# openmote32_2_0_1.net
KiCad netlist of a schematic drawn in EAGLE
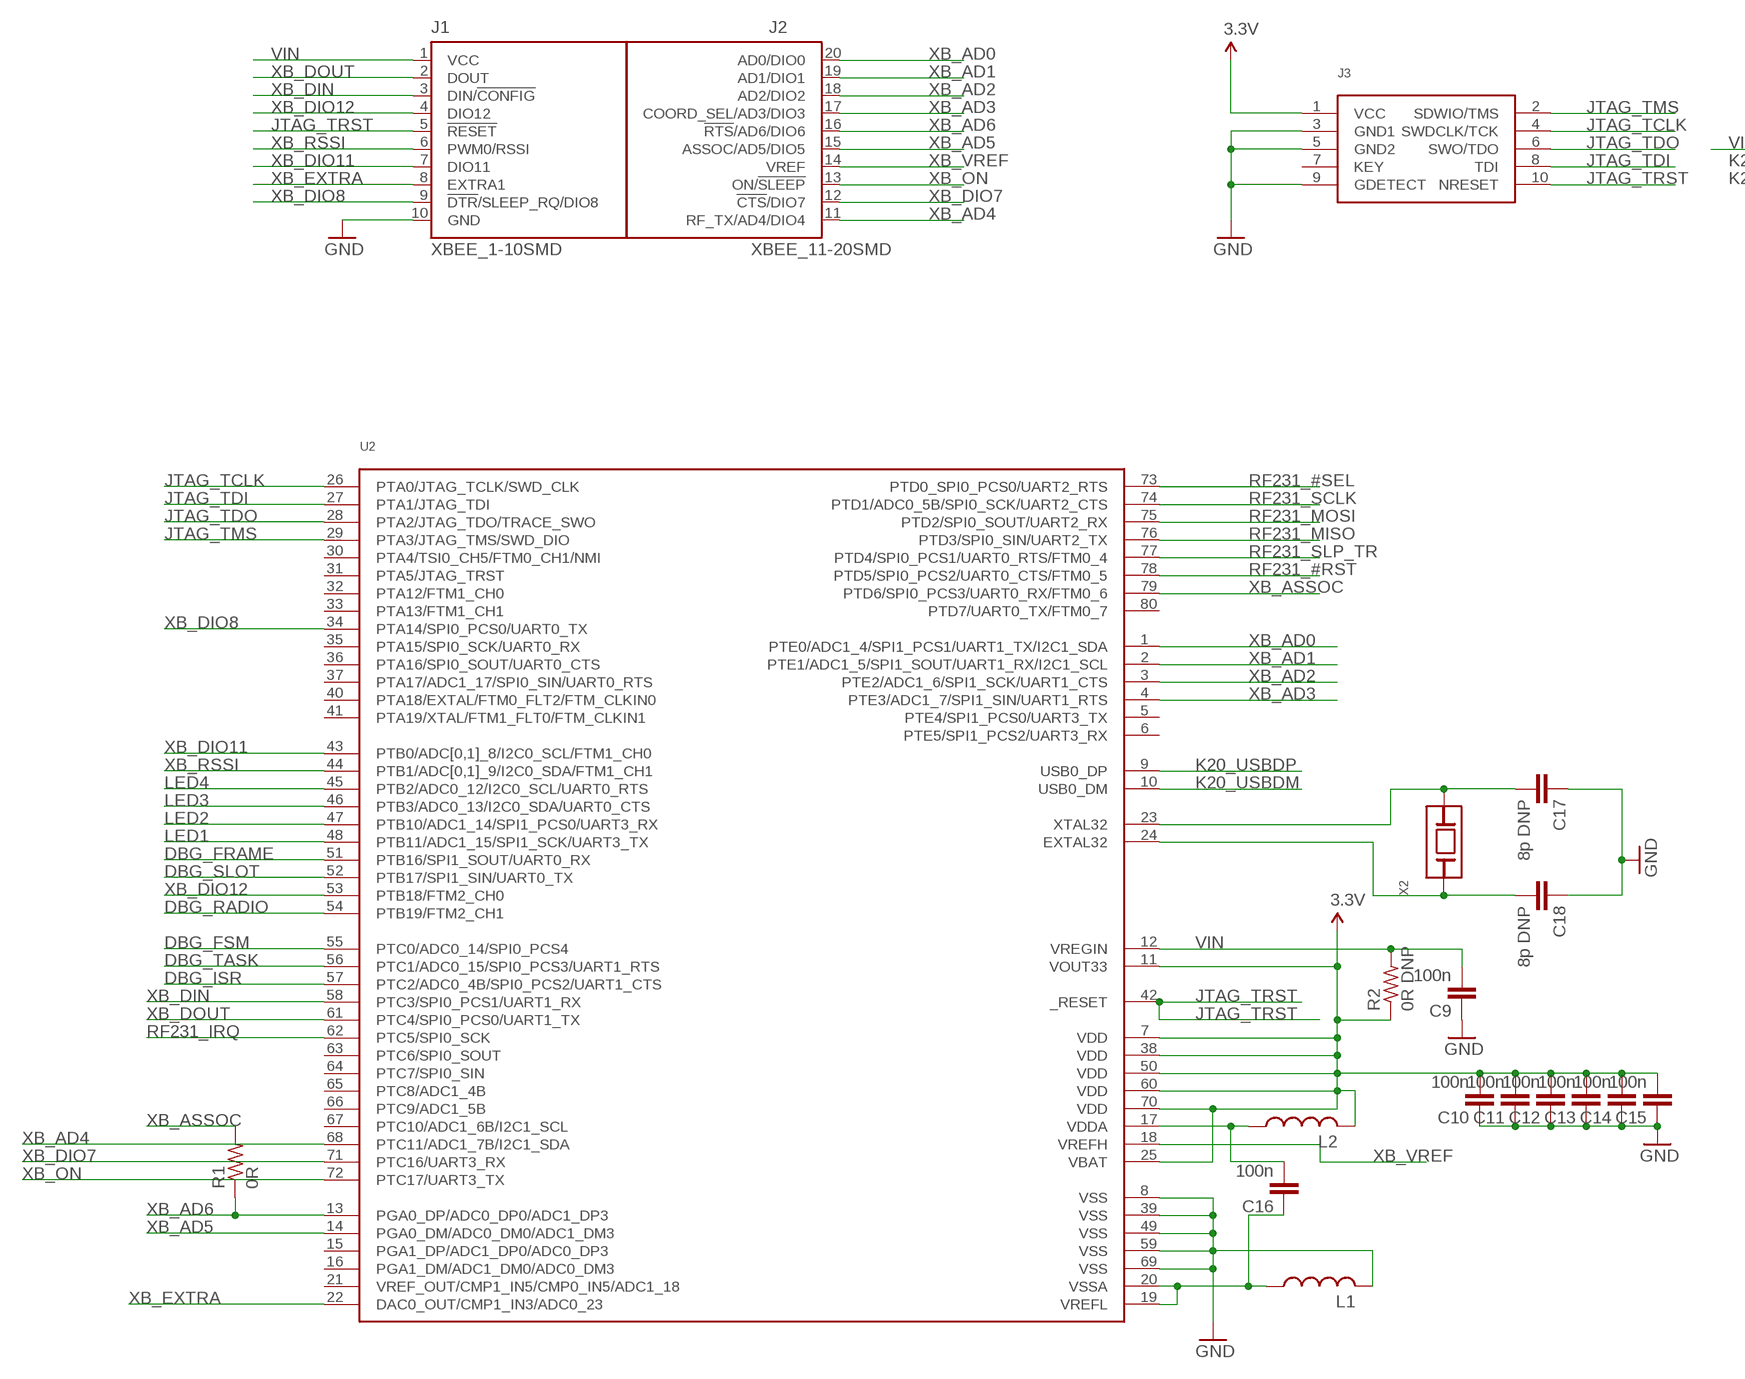
[diagram p0: schematic, sheet 1, part 1 of 2]
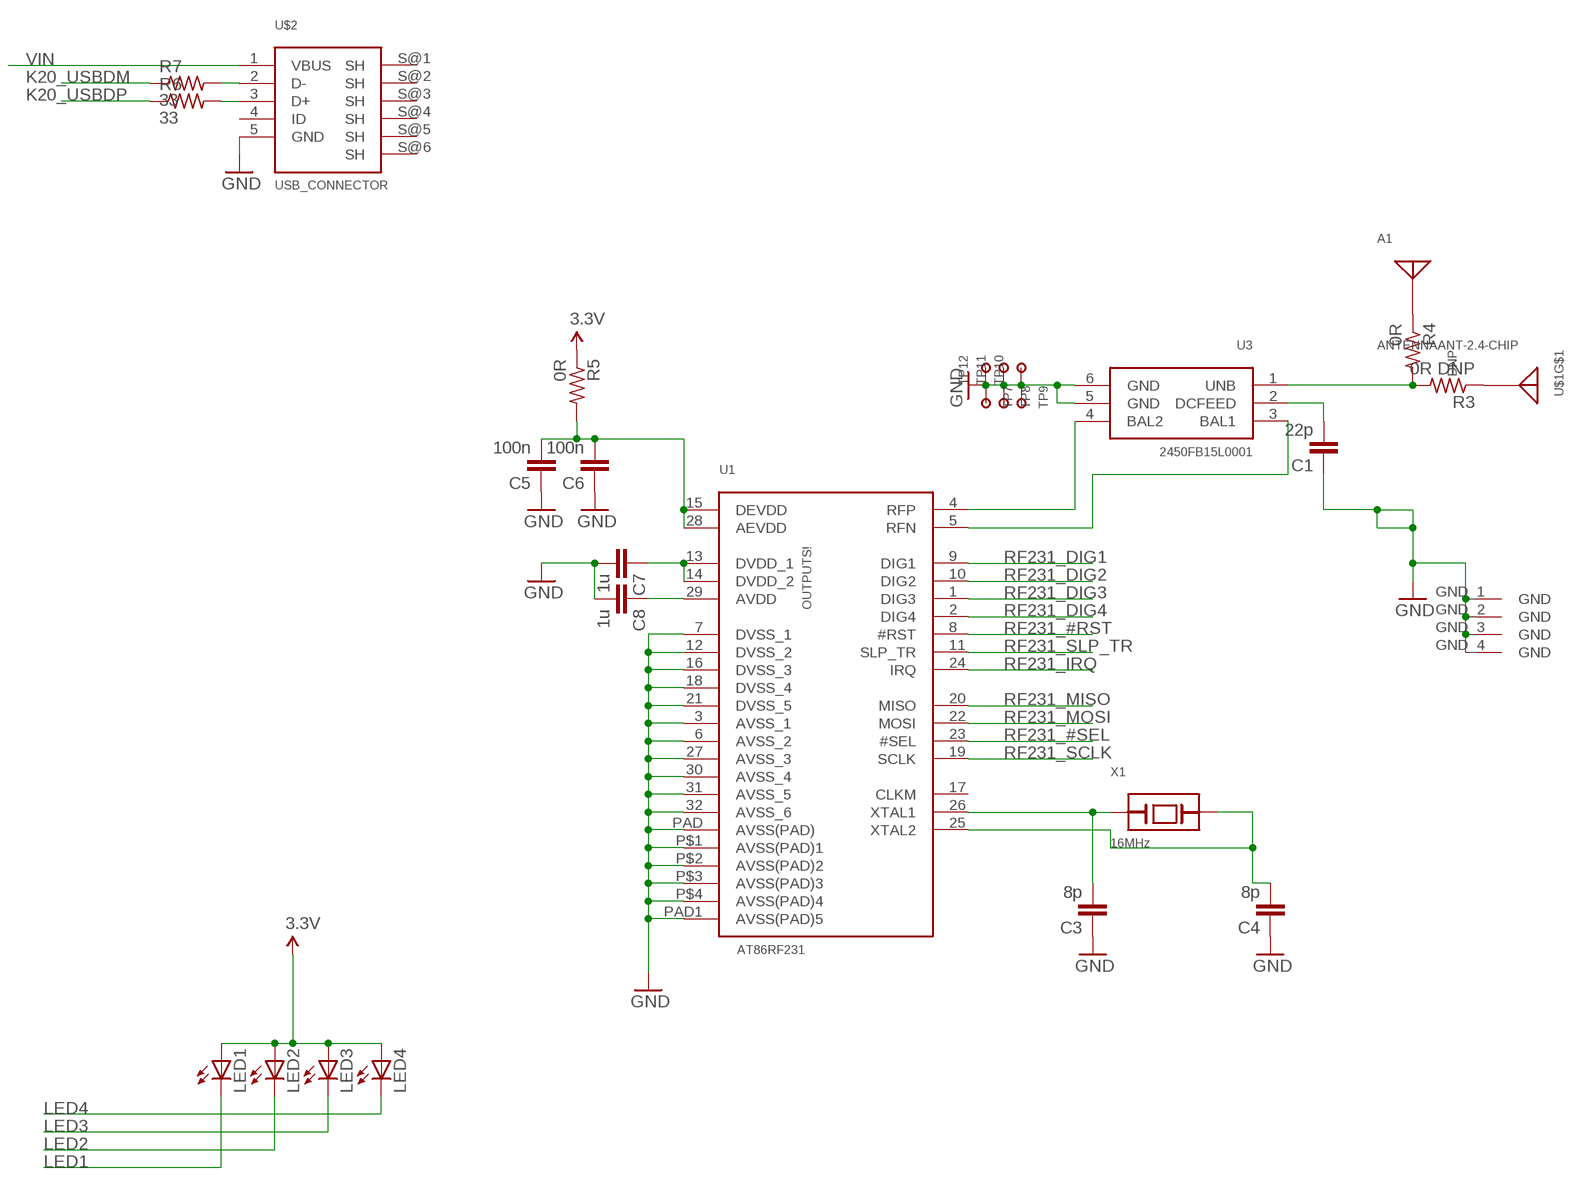
[diagram p1: schematic, sheet 1, part 2 of 2]

(export (version "E")
  (design (tool "Eeschema 10.0.6"))
  (components
    (comp (ref "A1")
      (value "ANTENNAANT-2.4-CHIP")
      (footprint "eagle-import:ANT-2.4-CHP")
      (libsource (lib "eagle-import") (part "ANTENNAANT-2.4-CHIP"))
    )
    (comp (ref "C1")
      (value "22p")
      (footprint "eagle-import:C0402")
      (libsource (lib "eagle-import") (part "CAP0402"))
    )
    (comp (ref "C3")
      (value "8p")
      (footprint "eagle-import:C0402")
      (libsource (lib "eagle-import") (part "CAP0402"))
    )
    (comp (ref "C4")
      (value "8p")
      (footprint "eagle-import:C0402")
      (libsource (lib "eagle-import") (part "CAP0402"))
    )
    (comp (ref "C5")
      (value "100n")
      (footprint "eagle-import:C0402")
      (libsource (lib "eagle-import") (part "CAP0402"))
    )
    (comp (ref "C6")
      (value "100n")
      (footprint "eagle-import:C0402")
      (libsource (lib "eagle-import") (part "CAP0402"))
    )
    (comp (ref "C7")
      (value "1u")
      (footprint "eagle-import:C0402")
      (libsource (lib "eagle-import") (part "CAP0402"))
    )
    (comp (ref "C8")
      (value "1u")
      (footprint "eagle-import:C0402")
      (libsource (lib "eagle-import") (part "CAP0402"))
    )
    (comp (ref "C9")
      (value "100n")
      (footprint "eagle-import:C0402")
      (libsource (lib "eagle-import") (part "CAP0402"))
    )
    (comp (ref "C10")
      (value "100n")
      (footprint "eagle-import:C0402")
      (libsource (lib "eagle-import") (part "CAP0402"))
    )
    (comp (ref "C11")
      (value "100n")
      (footprint "eagle-import:C0402")
      (libsource (lib "eagle-import") (part "CAP0402"))
    )
    (comp (ref "C12")
      (value "100n")
      (footprint "eagle-import:C0402")
      (libsource (lib "eagle-import") (part "CAP0402"))
    )
    (comp (ref "C13")
      (value "100n")
      (footprint "eagle-import:C0402")
      (libsource (lib "eagle-import") (part "CAP0402"))
    )
    (comp (ref "C14")
      (value "100n")
      (footprint "eagle-import:C0402")
      (libsource (lib "eagle-import") (part "CAP0402"))
    )
    (comp (ref "C15")
      (value "100n")
      (footprint "eagle-import:C0402")
      (libsource (lib "eagle-import") (part "CAP0402"))
    )
    (comp (ref "C16")
      (value "100n")
      (footprint "eagle-import:C0402")
      (libsource (lib "eagle-import") (part "CAP0402"))
    )
    (comp (ref "C17")
      (value "8p DNP")
      (footprint "eagle-import:C0402")
      (libsource (lib "eagle-import") (part "CAP0402"))
    )
    (comp (ref "C18")
      (value "8p DNP")
      (footprint "eagle-import:C0402")
      (libsource (lib "eagle-import") (part "CAP0402"))
    )
    (comp (ref "J1")
      (value "XBEE_1-10SMD")
      (footprint "eagle-import:XBEE_1-10+SMD")
      (libsource (lib "eagle-import") (part "XBEE_1-10SMD"))
    )
    (comp (ref "J2")
      (value "XBEE_11-20SMD")
      (footprint "eagle-import:XBEE_11-20+SMD")
      (libsource (lib "eagle-import") (part "XBEE_11-20SMD"))
    )
    (comp (ref "J3")
      (value "JTAG_CONNECTOR")
      (footprint "eagle-import:SMD-050-HEADER-2X5")
      (libsource (lib "eagle-import") (part "JTAG_CONNECTOR"))
    )
    (comp (ref "L1")
      (value "L-USL0402")
      (footprint "eagle-import:L0402")
      (libsource (lib "eagle-import") (part "L-USL0402"))
    )
    (comp (ref "L2")
      (value "L-USL0402")
      (footprint "eagle-import:L0402")
      (libsource (lib "eagle-import") (part "L-USL0402"))
    )
    (comp (ref "LED1")
      (value "LEDCHIPLED_0603")
      (footprint "eagle-import:CHIPLED_0603")
      (libsource (lib "eagle-import") (part "LEDCHIPLED_0603"))
    )
    (comp (ref "LED2")
      (value "LEDCHIPLED_0603")
      (footprint "eagle-import:CHIPLED_0603")
      (libsource (lib "eagle-import") (part "LEDCHIPLED_0603"))
    )
    (comp (ref "LED3")
      (value "LEDCHIPLED_0603")
      (footprint "eagle-import:CHIPLED_0603")
      (libsource (lib "eagle-import") (part "LEDCHIPLED_0603"))
    )
    (comp (ref "LED4")
      (value "LEDCHIPLED_0603")
      (footprint "eagle-import:CHIPLED_0603")
      (libsource (lib "eagle-import") (part "LEDCHIPLED_0603"))
    )
    (comp (ref "R1")
      (value "0R")
      (footprint "eagle-import:R0402")
      (libsource (lib "eagle-import") (part "R-US_R0402"))
    )
    (comp (ref "R2")
      (value "0R DNP")
      (footprint "eagle-import:R0402")
      (libsource (lib "eagle-import") (part "R-US_R0402"))
    )
    (comp (ref "R3")
      (value "0R DNP")
      (footprint "eagle-import:R0402")
      (libsource (lib "eagle-import") (part "R-US_R0402"))
    )
    (comp (ref "R4")
      (value "0R")
      (footprint "eagle-import:R0402")
      (libsource (lib "eagle-import") (part "R-US_R0402"))
    )
    (comp (ref "R5")
      (value "0R")
      (footprint "eagle-import:R0402")
      (libsource (lib "eagle-import") (part "R-US_R0402"))
    )
    (comp (ref "R6")
      (value "33")
      (footprint "eagle-import:R0402")
      (libsource (lib "eagle-import") (part "R-US_R0402"))
    )
    (comp (ref "R7")
      (value "33")
      (footprint "eagle-import:R0402")
      (libsource (lib "eagle-import") (part "R-US_R0402"))
    )
    (comp (ref "TP7")
      (value "TESTPOINTSMALLEST")
      (footprint "eagle-import:TESTPOINT")
      (libsource (lib "eagle-import") (part "TESTPOINTSMALLEST"))
    )
    (comp (ref "TP8")
      (value "TESTPOINTSMALLEST")
      (footprint "eagle-import:TESTPOINT")
      (libsource (lib "eagle-import") (part "TESTPOINTSMALLEST"))
    )
    (comp (ref "TP9")
      (value "TESTPOINTSMALLEST")
      (footprint "eagle-import:TESTPOINT")
      (libsource (lib "eagle-import") (part "TESTPOINTSMALLEST"))
    )
    (comp (ref "TP10")
      (value "TESTPOINTSMALLEST")
      (footprint "eagle-import:TESTPOINT")
      (libsource (lib "eagle-import") (part "TESTPOINTSMALLEST"))
    )
    (comp (ref "TP11")
      (value "TESTPOINTSMALLEST")
      (footprint "eagle-import:TESTPOINT")
      (libsource (lib "eagle-import") (part "TESTPOINTSMALLEST"))
    )
    (comp (ref "TP12")
      (value "TESTPOINTSMALLEST")
      (footprint "eagle-import:TESTPOINT")
      (libsource (lib "eagle-import") (part "TESTPOINTSMALLEST"))
    )
    (comp (ref "U$1")
      (value "DNP")
      (footprint "eagle-import:CONREVSMA003.031")
      (libsource (lib "eagle-import") (part "ANTENNA_W_GROUNDS"))
    )
    (comp (ref "U$2")
      (value "USB_CONNECTOR")
      (footprint "eagle-import:MICROUSB_10118192")
      (libsource (lib "eagle-import") (part "USB_CONNECTOR"))
    )
    (comp (ref "U1")
      (value "AT86RF231")
      (footprint "eagle-import:ATRF231_32QN2")
      (libsource (lib "eagle-import") (part "AT86RF231"))
    )
    (comp (ref "U2")
      (value "K20_80PIN")
      (footprint "eagle-import:K20_LQFP80")
      (libsource (lib "eagle-import") (part "K20_80PIN"))
    )
    (comp (ref "U3")
      (value "2450FB15L0001")
      (footprint "eagle-import:2450FB15L0001")
      (libsource (lib "eagle-import") (part "2450FB15L0001"))
    )
    (comp (ref "X1")
      (value "16MHz")
      (footprint "eagle-import:CX3225SA")
      (libsource (lib "eagle-import") (part "XTALCX3225SA"))
    )
    (comp (ref "X2")
      (value "XTALABS07")
      (footprint "eagle-import:ABS07")
      (libsource (lib "eagle-import") (part "XTALABS07"))
    )
  )
  (nets
    (net (code "1") (name "/DBG_FRAME") (class "Default")
      (node (ref "U2") (pin "51") (pinfunction "PTB16/SPI1_SOUT/UART0_RX_51") (pintype "bidirectional"))
    )
    (net (code "2") (name "/DBG_FSM") (class "Default")
      (node (ref "U2") (pin "55") (pinfunction "PTC0/ADC0_14/SPI0_PCS4_55") (pintype "bidirectional"))
    )
    (net (code "3") (name "/DBG_ISR") (class "Default")
      (node (ref "U2") (pin "57") (pinfunction "PTC2/ADC0_4B/SPI0_PCS2/UART1_CTS_57") (pintype "bidirectional"))
    )
    (net (code "4") (name "/DBG_RADIO") (class "Default")
      (node (ref "U2") (pin "54") (pinfunction "PTB19/FTM2_CH1_54") (pintype "bidirectional"))
    )
    (net (code "5") (name "/DBG_SLOT") (class "Default")
      (node (ref "U2") (pin "52") (pinfunction "PTB17/SPI1_SIN/UART0_TX_52") (pintype "bidirectional"))
    )
    (net (code "6") (name "/DBG_TASK") (class "Default")
      (node (ref "U2") (pin "56") (pinfunction "PTC1/ADC0_15/SPI0_PCS3/UART1_RTS_56") (pintype "bidirectional"))
    )
    (net (code "7") (name "/JTAG_TCLK") (class "Default")
      (node (ref "J3") (pin "4") (pinfunction "SWDCLK/TCK_4") (pintype "bidirectional"))
      (node (ref "U2") (pin "26") (pinfunction "PTA0/JTAG_TCLK/SWD_CLK_26") (pintype "bidirectional"))
    )
    (net (code "8") (name "/JTAG_TDI") (class "Default")
      (node (ref "J3") (pin "8") (pinfunction "TDI_8") (pintype "bidirectional"))
      (node (ref "U2") (pin "27") (pinfunction "PTA1/JTAG_TDI_27") (pintype "bidirectional"))
    )
    (net (code "9") (name "/JTAG_TDO") (class "Default")
      (node (ref "J3") (pin "6") (pinfunction "SWO/TDO_6") (pintype "bidirectional"))
      (node (ref "U2") (pin "28") (pinfunction "PTA2/JTAG_TDO/TRACE_SWO_28") (pintype "bidirectional"))
    )
    (net (code "10") (name "/JTAG_TMS") (class "Default")
      (node (ref "J3") (pin "2") (pinfunction "SDWIO/TMS_2") (pintype "bidirectional"))
      (node (ref "U2") (pin "29") (pinfunction "PTA3/JTAG_TMS/SWD_DIO_29") (pintype "bidirectional"))
    )
    (net (code "11") (name "/JTAG_TRST") (class "Default")
      (node (ref "J1") (pin "5") (pinfunction "~{RESET}_5") (pintype "input"))
      (node (ref "J3") (pin "10") (pinfunction "NRESET_10") (pintype "bidirectional"))
      (node (ref "U2") (pin "42") (pinfunction "_RESET_42") (pintype "bidirectional"))
    )
    (net (code "12") (name "/K20_USBDM") (class "Default")
      (node (ref "R7") (pin "1") (pinfunction "1_1") (pintype "passive"))
      (node (ref "U2") (pin "10") (pinfunction "USB0_DM_10") (pintype "bidirectional"))
    )
    (net (code "13") (name "/K20_USBDP") (class "Default")
      (node (ref "R6") (pin "1") (pinfunction "1_1") (pintype "passive"))
      (node (ref "U2") (pin "9") (pinfunction "USB0_DP_9") (pintype "bidirectional"))
    )
    (net (code "14") (name "/LED1") (class "Default")
      (node (ref "LED1") (pin "C") (pinfunction "C_C") (pintype "passive"))
      (node (ref "U2") (pin "48") (pinfunction "PTB11/ADC1_15/SPI1_SCK/UART3_TX_48") (pintype "bidirectional"))
    )
    (net (code "15") (name "/LED2") (class "Default")
      (node (ref "LED2") (pin "C") (pinfunction "C_C") (pintype "passive"))
      (node (ref "U2") (pin "47") (pinfunction "PTB10/ADC1_14/SPI1_PCS0/UART3_RX_47") (pintype "bidirectional"))
    )
    (net (code "16") (name "/LED3") (class "Default")
      (node (ref "LED3") (pin "C") (pinfunction "C_C") (pintype "passive"))
      (node (ref "U2") (pin "46") (pinfunction "PTB3/ADC0_13/I2C0_SDA/UART0_CTS_46") (pintype "bidirectional"))
    )
    (net (code "17") (name "/LED4") (class "Default")
      (node (ref "LED4") (pin "C") (pinfunction "C_C") (pintype "passive"))
      (node (ref "U2") (pin "45") (pinfunction "PTB2/ADC0_12/I2C0_SCL/UART0_RTS_45") (pintype "bidirectional"))
    )
    (net (code "18") (name "/RF231_#RST") (class "Default")
      (node (ref "U1") (pin "8") (pinfunction "#RST_8") (pintype "bidirectional"))
      (node (ref "U2") (pin "78") (pinfunction "PTD5/SPI0_PCS2/UART0_CTS/FTM0_5_78") (pintype "bidirectional"))
    )
    (net (code "19") (name "/RF231_#SEL") (class "Default")
      (node (ref "U1") (pin "23") (pinfunction "#SEL_23") (pintype "bidirectional"))
      (node (ref "U2") (pin "73") (pinfunction "PTD0_SPI0_PCS0/UART2_RTS_73") (pintype "bidirectional"))
    )
    (net (code "20") (name "/RF231_DIG1") (class "Default")
      (node (ref "U1") (pin "9") (pinfunction "DIG1_9") (pintype "bidirectional"))
    )
    (net (code "21") (name "/RF231_DIG2") (class "Default")
      (node (ref "U1") (pin "10") (pinfunction "DIG2_10") (pintype "bidirectional"))
    )
    (net (code "22") (name "/RF231_DIG3") (class "Default")
      (node (ref "U1") (pin "1") (pinfunction "DIG3_1") (pintype "bidirectional"))
    )
    (net (code "23") (name "/RF231_DIG4") (class "Default")
      (node (ref "U1") (pin "2") (pinfunction "DIG4_2") (pintype "bidirectional"))
    )
    (net (code "24") (name "/RF231_IRQ") (class "Default")
      (node (ref "U1") (pin "24") (pinfunction "IRQ_24") (pintype "bidirectional"))
      (node (ref "U2") (pin "62") (pinfunction "PTC5/SPI0_SCK_62") (pintype "bidirectional"))
    )
    (net (code "25") (name "/RF231_MISO") (class "Default")
      (node (ref "U1") (pin "20") (pinfunction "MISO_20") (pintype "bidirectional"))
      (node (ref "U2") (pin "76") (pinfunction "PTD3/SPI0_SIN/UART2_TX_76") (pintype "bidirectional"))
    )
    (net (code "26") (name "/RF231_MOSI") (class "Default")
      (node (ref "U1") (pin "22") (pinfunction "MOSI_22") (pintype "bidirectional"))
      (node (ref "U2") (pin "75") (pinfunction "PTD2/SPI0_SOUT/UART2_RX_75") (pintype "bidirectional"))
    )
    (net (code "27") (name "/RF231_SCLK") (class "Default")
      (node (ref "U1") (pin "19") (pinfunction "SCLK_19") (pintype "bidirectional"))
      (node (ref "U2") (pin "74") (pinfunction "PTD1/ADC0_5B/SPI0_SCK/UART2_CTS_74") (pintype "bidirectional"))
    )
    (net (code "28") (name "/RF231_SLP_TR") (class "Default")
      (node (ref "U1") (pin "11") (pinfunction "SLP_TR_11") (pintype "bidirectional"))
      (node (ref "U2") (pin "77") (pinfunction "PTD4/SPI0_PCS1/UART0_RTS/FTM0_4_77") (pintype "bidirectional"))
    )
    (net (code "29") (name "/VIN") (class "Default")
      (node (ref "C9") (pin "2") (pinfunction "2_2") (pintype "passive"))
      (node (ref "J1") (pin "1") (pinfunction "VCC_1") (pintype "power_in"))
      (node (ref "R2") (pin "2") (pinfunction "2_2") (pintype "passive"))
      (node (ref "U$2") (pin "1") (pinfunction "VBUS_1") (pintype "bidirectional"))
      (node (ref "U2") (pin "12") (pinfunction "VREGIN_12") (pintype "bidirectional"))
    )
    (net (code "30") (name "/XB_AD0") (class "Default")
      (node (ref "J2") (pin "20") (pinfunction "AD0/DIO0_20") (pintype "bidirectional"))
      (node (ref "U2") (pin "1") (pinfunction "PTE0/ADC1_4/SPI1_PCS1/UART1_TX/I2C1_SDA_1") (pintype "bidirectional"))
    )
    (net (code "31") (name "/XB_AD1") (class "Default")
      (node (ref "J2") (pin "19") (pinfunction "AD1/DIO1_19") (pintype "bidirectional"))
      (node (ref "U2") (pin "2") (pinfunction "PTE1/ADC1_5/SPI1_SOUT/UART1_RX/I2C1_SCL_2") (pintype "bidirectional"))
    )
    (net (code "32") (name "/XB_AD2") (class "Default")
      (node (ref "J2") (pin "18") (pinfunction "AD2/DIO2_18") (pintype "bidirectional"))
      (node (ref "U2") (pin "3") (pinfunction "PTE2/ADC1_6/SPI1_SCK/UART1_CTS_3") (pintype "bidirectional"))
    )
    (net (code "33") (name "/XB_AD3") (class "Default")
      (node (ref "J2") (pin "17") (pinfunction "COORD_SEL/AD3/DIO3_17") (pintype "bidirectional"))
      (node (ref "U2") (pin "4") (pinfunction "PTE3/ADC1_7/SPI1_SIN/UART1_RTS_4") (pintype "bidirectional"))
    )
    (net (code "34") (name "/XB_AD4") (class "Default")
      (node (ref "J2") (pin "11") (pinfunction "RF_TX/AD4/DIO4_11") (pintype "bidirectional"))
      (node (ref "U2") (pin "68") (pinfunction "PTC11/ADC1_7B/I2C1_SDA_68") (pintype "bidirectional"))
    )
    (net (code "35") (name "/XB_AD5") (class "Default")
      (node (ref "J2") (pin "15") (pinfunction "ASSOC/AD5/DIO5_15") (pintype "bidirectional"))
      (node (ref "U2") (pin "14") (pinfunction "PGA0_DM/ADC0_DM0/ADC1_DM3_14") (pintype "bidirectional"))
    )
    (net (code "36") (name "/XB_AD6") (class "Default")
      (node (ref "J2") (pin "16") (pinfunction "~{RTS}/AD6/DIO6_16") (pintype "bidirectional"))
      (node (ref "R1") (pin "1") (pinfunction "1_1") (pintype "passive"))
      (node (ref "U2") (pin "13") (pinfunction "PGA0_DP/ADC0_DP0/ADC1_DP3_13") (pintype "bidirectional"))
    )
    (net (code "37") (name "/XB_ASSOC") (class "Default")
      (node (ref "R1") (pin "2") (pinfunction "2_2") (pintype "passive"))
      (node (ref "U2") (pin "79") (pinfunction "PTD6/SPI0_PCS3/UART0_RX/FTM0_6_79") (pintype "bidirectional"))
    )
    (net (code "38") (name "/XB_DIN") (class "Default")
      (node (ref "J1") (pin "3") (pinfunction "DIN/~{CONFIG}_3") (pintype "input"))
      (node (ref "U2") (pin "58") (pinfunction "PTC3/SPI0_PCS1/UART1_RX_58") (pintype "bidirectional"))
    )
    (net (code "39") (name "/XB_DIO7") (class "Default")
      (node (ref "J2") (pin "12") (pinfunction "~{CTS}/DIO7_12") (pintype "bidirectional"))
      (node (ref "U2") (pin "71") (pinfunction "PTC16/UART3_RX_71") (pintype "bidirectional"))
    )
    (net (code "40") (name "/XB_DIO8") (class "Default")
      (node (ref "J1") (pin "9") (pinfunction "~{DTR}/SLEEP_RQ/DIO8_9") (pintype "bidirectional"))
      (node (ref "U2") (pin "34") (pinfunction "PTA14/SPI0_PCS0/UART0_TX_34") (pintype "bidirectional"))
    )
    (net (code "41") (name "/XB_DIO11") (class "Default")
      (node (ref "J1") (pin "7") (pinfunction "DIO11_7") (pintype "output"))
      (node (ref "U2") (pin "43") (pinfunction "PTB0/ADC[0,1]_8/I2C0_SCL/FTM1_CH0_43") (pintype "bidirectional"))
    )
    (net (code "42") (name "/XB_DIO12") (class "Default")
      (node (ref "J1") (pin "4") (pinfunction "DIO12_4") (pintype "bidirectional"))
      (node (ref "U2") (pin "53") (pinfunction "PTB18/FTM2_CH0_53") (pintype "bidirectional"))
    )
    (net (code "43") (name "/XB_DOUT") (class "Default")
      (node (ref "J1") (pin "2") (pinfunction "DOUT_2") (pintype "output"))
      (node (ref "U2") (pin "61") (pinfunction "PTC4/SPI0_PCS0/UART1_TX_61") (pintype "bidirectional"))
    )
    (net (code "44") (name "/XB_EXTRA") (class "Default")
      (node (ref "J1") (pin "8") (pinfunction "EXTRA1_8") (pintype "bidirectional"))
      (node (ref "U2") (pin "22") (pinfunction "DAC0_OUT/CMP1_IN3/ADC0_23_22") (pintype "bidirectional"))
    )
    (net (code "45") (name "/XB_ON") (class "Default")
      (node (ref "J2") (pin "13") (pinfunction "ON/~{SLEEP}_13") (pintype "output"))
      (node (ref "U2") (pin "72") (pinfunction "PTC17/UART3_TX_72") (pintype "bidirectional"))
    )
    (net (code "46") (name "/XB_RSSI") (class "Default")
      (node (ref "J1") (pin "6") (pinfunction "PWM0/RSSI_6") (pintype "output"))
      (node (ref "U2") (pin "44") (pinfunction "PTB1/ADC[0,1]_9/I2C0_SDA/FTM1_CH1_44") (pintype "bidirectional"))
    )
    (net (code "47") (name "/XB_VREF") (class "Default")
      (node (ref "J2") (pin "14") (pinfunction "VREF_14") (pintype "input"))
      (node (ref "U2") (pin "18") (pinfunction "VREFH_18") (pintype "bidirectional"))
    )
    (net (code "48") (name "3.3V") (class "Default")
      (node (ref "C10") (pin "2") (pinfunction "2_2") (pintype "passive"))
      (node (ref "C11") (pin "2") (pinfunction "2_2") (pintype "passive"))
      (node (ref "C12") (pin "2") (pinfunction "2_2") (pintype "passive"))
      (node (ref "C13") (pin "2") (pinfunction "2_2") (pintype "passive"))
      (node (ref "C14") (pin "2") (pinfunction "2_2") (pintype "passive"))
      (node (ref "C15") (pin "2") (pinfunction "2_2") (pintype "passive"))
      (node (ref "J3") (pin "1") (pinfunction "VCC_1") (pintype "bidirectional"))
      (node (ref "L2") (pin "2") (pinfunction "2_2") (pintype "passive"))
      (node (ref "LED1") (pin "A") (pinfunction "A_A") (pintype "passive"))
      (node (ref "LED2") (pin "A") (pinfunction "A_A") (pintype "passive"))
      (node (ref "LED3") (pin "A") (pinfunction "A_A") (pintype "passive"))
      (node (ref "LED4") (pin "A") (pinfunction "A_A") (pintype "passive"))
      (node (ref "R2") (pin "1") (pinfunction "1_1") (pintype "passive"))
      (node (ref "R5") (pin "1") (pinfunction "1_1") (pintype "passive"))
      (node (ref "U2") (pin "11") (pinfunction "VOUT33_11") (pintype "bidirectional"))
      (node (ref "U2") (pin "25") (pinfunction "VBAT_25") (pintype "bidirectional"))
      (node (ref "U2") (pin "38") (pinfunction "VDD_38") (pintype "bidirectional"))
      (node (ref "U2") (pin "50") (pinfunction "VDD_50") (pintype "bidirectional"))
      (node (ref "U2") (pin "60") (pinfunction "VDD_60") (pintype "bidirectional"))
      (node (ref "U2") (pin "7") (pinfunction "VDD_7") (pintype "bidirectional"))
      (node (ref "U2") (pin "70") (pinfunction "VDD_70") (pintype "bidirectional"))
    )
    (net (code "49") (name "GND") (class "Default")
      (node (ref "C1") (pin "1") (pinfunction "1_1") (pintype "passive"))
      (node (ref "C10") (pin "1") (pinfunction "1_1") (pintype "passive"))
      (node (ref "C11") (pin "1") (pinfunction "1_1") (pintype "passive"))
      (node (ref "C12") (pin "1") (pinfunction "1_1") (pintype "passive"))
      (node (ref "C13") (pin "1") (pinfunction "1_1") (pintype "passive"))
      (node (ref "C14") (pin "1") (pinfunction "1_1") (pintype "passive"))
      (node (ref "C15") (pin "1") (pinfunction "1_1") (pintype "passive"))
      (node (ref "C17") (pin "1") (pinfunction "1_1") (pintype "passive"))
      (node (ref "C18") (pin "1") (pinfunction "1_1") (pintype "passive"))
      (node (ref "C3") (pin "1") (pinfunction "1_1") (pintype "passive"))
      (node (ref "C4") (pin "1") (pinfunction "1_1") (pintype "passive"))
      (node (ref "C5") (pin "1") (pinfunction "1_1") (pintype "passive"))
      (node (ref "C6") (pin "1") (pinfunction "1_1") (pintype "passive"))
      (node (ref "C7") (pin "2") (pinfunction "2_2") (pintype "passive"))
      (node (ref "C8") (pin "2") (pinfunction "2_2") (pintype "passive"))
      (node (ref "C9") (pin "1") (pinfunction "1_1") (pintype "passive"))
      (node (ref "J1") (pin "10") (pinfunction "GND_10") (pintype "power_in"))
      (node (ref "J3") (pin "3") (pinfunction "GND1_3") (pintype "bidirectional"))
      (node (ref "J3") (pin "5") (pinfunction "GND2_5") (pintype "bidirectional"))
      (node (ref "J3") (pin "9") (pinfunction "GDETECT_9") (pintype "bidirectional"))
      (node (ref "L1") (pin "2") (pinfunction "2_2") (pintype "passive"))
      (node (ref "TP10") (pin "P$1") (pinfunction "P$1_P$1") (pintype "bidirectional"))
      (node (ref "TP11") (pin "P$1") (pinfunction "P$1_P$1") (pintype "bidirectional"))
      (node (ref "TP12") (pin "P$1") (pinfunction "P$1_P$1") (pintype "bidirectional"))
      (node (ref "TP7") (pin "P$1") (pinfunction "P$1_P$1") (pintype "bidirectional"))
      (node (ref "TP8") (pin "P$1") (pinfunction "P$1_P$1") (pintype "bidirectional"))
      (node (ref "TP9") (pin "P$1") (pinfunction "P$1_P$1") (pintype "bidirectional"))
      (node (ref "U$1") (pin "GND_1") (pinfunction "GND_GND_1") (pintype "power_in"))
      (node (ref "U$1") (pin "GND_2") (pinfunction "GND_GND_2") (pintype "power_in"))
      (node (ref "U$1") (pin "GND_3") (pinfunction "GND_GND_3") (pintype "power_in"))
      (node (ref "U$1") (pin "GND_4") (pinfunction "GND_GND_4") (pintype "power_in"))
      (node (ref "U$2") (pin "5") (pinfunction "GND_5") (pintype "bidirectional"))
      (node (ref "U1") (pin "12") (pinfunction "DVSS_2_12") (pintype "bidirectional"))
      (node (ref "U1") (pin "16") (pinfunction "DVSS_3_16") (pintype "bidirectional"))
      (node (ref "U1") (pin "18") (pinfunction "DVSS_4_18") (pintype "bidirectional"))
      (node (ref "U1") (pin "21") (pinfunction "DVSS_5_21") (pintype "bidirectional"))
      (node (ref "U1") (pin "27") (pinfunction "AVSS_3_27") (pintype "bidirectional"))
      (node (ref "U1") (pin "3") (pinfunction "AVSS_1_3") (pintype "bidirectional"))
      (node (ref "U1") (pin "30") (pinfunction "AVSS_4_30") (pintype "bidirectional"))
      (node (ref "U1") (pin "31") (pinfunction "AVSS_5_31") (pintype "bidirectional"))
      (node (ref "U1") (pin "32") (pinfunction "AVSS_6_32") (pintype "bidirectional"))
      (node (ref "U1") (pin "6") (pinfunction "AVSS_2_6") (pintype "bidirectional"))
      (node (ref "U1") (pin "7") (pinfunction "DVSS_1_7") (pintype "bidirectional"))
      (node (ref "U1") (pin "P$1") (pinfunction "AVSS(PAD)1_P$1") (pintype "bidirectional"))
      (node (ref "U1") (pin "P$2") (pinfunction "AVSS(PAD)2_P$2") (pintype "bidirectional"))
      (node (ref "U1") (pin "P$3") (pinfunction "AVSS(PAD)3_P$3") (pintype "bidirectional"))
      (node (ref "U1") (pin "P$4") (pinfunction "AVSS(PAD)4_P$4") (pintype "bidirectional"))
      (node (ref "U1") (pin "PAD") (pinfunction "AVSS(PAD)_PAD") (pintype "bidirectional"))
      (node (ref "U1") (pin "PAD1") (pinfunction "AVSS(PAD)5_PAD1") (pintype "bidirectional"))
      (node (ref "U2") (pin "39") (pinfunction "VSS_39") (pintype "bidirectional"))
      (node (ref "U2") (pin "49") (pinfunction "VSS_49") (pintype "bidirectional"))
      (node (ref "U2") (pin "59") (pinfunction "VSS_59") (pintype "bidirectional"))
      (node (ref "U2") (pin "69") (pinfunction "VSS_69") (pintype "bidirectional"))
      (node (ref "U2") (pin "8") (pinfunction "VSS_8") (pintype "bidirectional"))
      (node (ref "U3") (pin "5") (pinfunction "GND_5") (pintype "bidirectional"))
      (node (ref "U3") (pin "6") (pinfunction "GND_6") (pintype "bidirectional"))
    )
    (net (code "50") (name "Net-(A1-P$1)") (class "Default")
      (node (ref "A1") (pin "CON") (pinfunction "P$1_CON") (pintype "bidirectional"))
      (node (ref "R4") (pin "1") (pinfunction "1_1") (pintype "passive"))
    )
    (net (code "51") (name "Net-(U$1A-P$1)") (class "Default")
      (node (ref "R3") (pin "1") (pinfunction "1_1") (pintype "passive"))
      (node (ref "U$1") (pin "CON") (pinfunction "P$1_CON") (pintype "bidirectional"))
    )
    (net (code "52") (name "Net-(U$2-D+)") (class "Default")
      (node (ref "R6") (pin "2") (pinfunction "2_2") (pintype "passive"))
      (node (ref "U$2") (pin "3") (pinfunction "D+_3") (pintype "bidirectional"))
    )
    (net (code "53") (name "Net-(U$2-D-)") (class "Default")
      (node (ref "R7") (pin "2") (pinfunction "2_2") (pintype "passive"))
      (node (ref "U$2") (pin "2") (pinfunction "D-_2") (pintype "bidirectional"))
    )
    (net (code "54") (name "Net-(U1-AEVDD)") (class "Default")
      (node (ref "C5") (pin "2") (pinfunction "2_2") (pintype "passive"))
      (node (ref "C6") (pin "2") (pinfunction "2_2") (pintype "passive"))
      (node (ref "R5") (pin "2") (pinfunction "2_2") (pintype "passive"))
      (node (ref "U1") (pin "15") (pinfunction "DEVDD_15") (pintype "bidirectional"))
      (node (ref "U1") (pin "28") (pinfunction "AEVDD_28") (pintype "bidirectional"))
    )
    (net (code "55") (name "Net-(U1-AVDD)") (class "Default")
      (node (ref "C8") (pin "1") (pinfunction "1_1") (pintype "passive"))
      (node (ref "U1") (pin "29") (pinfunction "AVDD_29") (pintype "bidirectional"))
    )
    (net (code "56") (name "Net-(U1-DVDD_1)") (class "Default")
      (node (ref "C7") (pin "1") (pinfunction "1_1") (pintype "passive"))
      (node (ref "U1") (pin "13") (pinfunction "DVDD_1_13") (pintype "bidirectional"))
      (node (ref "U1") (pin "14") (pinfunction "DVDD_2_14") (pintype "bidirectional"))
    )
    (net (code "57") (name "Net-(U1-RFN)") (class "Default")
      (node (ref "U1") (pin "5") (pinfunction "RFN_5") (pintype "bidirectional"))
      (node (ref "U3") (pin "3") (pinfunction "BAL1_3") (pintype "bidirectional"))
    )
    (net (code "58") (name "Net-(U1-RFP)") (class "Default")
      (node (ref "U1") (pin "4") (pinfunction "RFP_4") (pintype "bidirectional"))
      (node (ref "U3") (pin "4") (pinfunction "BAL2_4") (pintype "bidirectional"))
    )
    (net (code "59") (name "Net-(U1-XTAL1)") (class "Default")
      (node (ref "C3") (pin "2") (pinfunction "2_2") (pintype "passive"))
      (node (ref "U1") (pin "26") (pinfunction "XTAL1_26") (pintype "bidirectional"))
      (node (ref "X1") (pin "3") (pinfunction "A_3") (pintype "bidirectional"))
    )
    (net (code "60") (name "Net-(U1-XTAL2)") (class "Default")
      (node (ref "C4") (pin "2") (pinfunction "2_2") (pintype "passive"))
      (node (ref "U1") (pin "25") (pinfunction "XTAL2_25") (pintype "bidirectional"))
      (node (ref "X1") (pin "1") (pinfunction "B_1") (pintype "bidirectional"))
    )
    (net (code "61") (name "Net-(U2-EXTAL32)") (class "Default")
      (node (ref "C18") (pin "2") (pinfunction "2_2") (pintype "passive"))
      (node (ref "U2") (pin "24") (pinfunction "EXTAL32_24") (pintype "bidirectional"))
      (node (ref "X2") (pin "1") (pinfunction "A_1") (pintype "bidirectional"))
    )
    (net (code "62") (name "Net-(U2-VDDA)") (class "Default")
      (node (ref "C16") (pin "2") (pinfunction "2_2") (pintype "passive"))
      (node (ref "L2") (pin "1") (pinfunction "1_1") (pintype "passive"))
      (node (ref "U2") (pin "17") (pinfunction "VDDA_17") (pintype "bidirectional"))
    )
    (net (code "63") (name "Net-(U2-VREFL)") (class "Default")
      (node (ref "C16") (pin "1") (pinfunction "1_1") (pintype "passive"))
      (node (ref "L1") (pin "1") (pinfunction "1_1") (pintype "passive"))
      (node (ref "U2") (pin "19") (pinfunction "VREFL_19") (pintype "bidirectional"))
      (node (ref "U2") (pin "20") (pinfunction "VSSA_20") (pintype "bidirectional"))
    )
    (net (code "64") (name "Net-(U2-XTAL32)") (class "Default")
      (node (ref "C17") (pin "2") (pinfunction "2_2") (pintype "passive"))
      (node (ref "U2") (pin "23") (pinfunction "XTAL32_23") (pintype "bidirectional"))
      (node (ref "X2") (pin "2") (pinfunction "B_2") (pintype "bidirectional"))
    )
    (net (code "65") (name "Net-(U3-DCFEED)") (class "Default")
      (node (ref "C1") (pin "2") (pinfunction "2_2") (pintype "passive"))
      (node (ref "U3") (pin "2") (pinfunction "DCFEED_2") (pintype "bidirectional"))
    )
    (net (code "66") (name "Net-(U3-UNB)") (class "Default")
      (node (ref "R3") (pin "2") (pinfunction "2_2") (pintype "passive"))
      (node (ref "R4") (pin "2") (pinfunction "2_2") (pintype "passive"))
      (node (ref "U3") (pin "1") (pinfunction "UNB_1") (pintype "bidirectional"))
    )
    (net (code "67") (name "unconnected-(J3-KEY-Pad7)") (class "Default")
      (node (ref "J3") (pin "7") (pinfunction "KEY_7") (pintype "bidirectional"))
    )
    (net (code "68") (name "unconnected-(U$2-ID-Pad4)") (class "Default")
      (node (ref "U$2") (pin "4") (pinfunction "ID_4") (pintype "bidirectional"))
    )
    (net (code "69") (name "unconnected-(U$2-SH-PadS@1)") (class "Default")
      (node (ref "U$2") (pin "S@1") (pinfunction "SH_S@1") (pintype "bidirectional"))
    )
    (net (code "70") (name "unconnected-(U$2-SH-PadS@2)") (class "Default")
      (node (ref "U$2") (pin "S@2") (pinfunction "SH_S@2") (pintype "bidirectional"))
    )
    (net (code "71") (name "unconnected-(U$2-SH-PadS@3)") (class "Default")
      (node (ref "U$2") (pin "S@3") (pinfunction "SH_S@3") (pintype "bidirectional"))
    )
    (net (code "72") (name "unconnected-(U$2-SH-PadS@4)") (class "Default")
      (node (ref "U$2") (pin "S@4") (pinfunction "SH_S@4") (pintype "bidirectional"))
    )
    (net (code "73") (name "unconnected-(U$2-SH-PadS@5)") (class "Default")
      (node (ref "U$2") (pin "S@5") (pinfunction "SH_S@5") (pintype "bidirectional"))
    )
    (net (code "74") (name "unconnected-(U$2-SH-PadS@6)") (class "Default")
      (node (ref "U$2") (pin "S@6") (pinfunction "SH_S@6") (pintype "bidirectional"))
    )
    (net (code "75") (name "unconnected-(U1-CLKM-Pad17)") (class "Default")
      (node (ref "U1") (pin "17") (pinfunction "CLKM_17") (pintype "bidirectional"))
    )
    (net (code "76") (name "unconnected-(U2-PGA1_DM{slash}ADC1_DM0{slash}ADC0_DM3-Pad16)") (class "Default")
      (node (ref "U2") (pin "16") (pinfunction "PGA1_DM/ADC1_DM0/ADC0_DM3_16") (pintype "bidirectional"))
    )
    (net (code "77") (name "unconnected-(U2-PGA1_DP{slash}ADC1_DP0{slash}ADC0_DP3-Pad15)") (class "Default")
      (node (ref "U2") (pin "15") (pinfunction "PGA1_DP/ADC1_DP0/ADC0_DP3_15") (pintype "bidirectional"))
    )
    (net (code "78") (name "unconnected-(U2-PTA4{slash}TSI0_CH5{slash}FTM0_CH1{slash}NMI-Pad30)") (class "Default")
      (node (ref "U2") (pin "30") (pinfunction "PTA4/TSI0_CH5/FTM0_CH1/NMI_30") (pintype "bidirectional"))
    )
    (net (code "79") (name "unconnected-(U2-PTA5{slash}JTAG_TRST-Pad31)") (class "Default")
      (node (ref "U2") (pin "31") (pinfunction "PTA5/JTAG_TRST_31") (pintype "bidirectional"))
    )
    (net (code "80") (name "unconnected-(U2-PTA12{slash}FTM1_CH0-Pad32)") (class "Default")
      (node (ref "U2") (pin "32") (pinfunction "PTA12/FTM1_CH0_32") (pintype "bidirectional"))
    )
    (net (code "81") (name "unconnected-(U2-PTA13{slash}FTM1_CH1-Pad33)") (class "Default")
      (node (ref "U2") (pin "33") (pinfunction "PTA13/FTM1_CH1_33") (pintype "bidirectional"))
    )
    (net (code "82") (name "unconnected-(U2-PTA15{slash}SPI0_SCK{slash}UART0_RX-Pad35)") (class "Default")
      (node (ref "U2") (pin "35") (pinfunction "PTA15/SPI0_SCK/UART0_RX_35") (pintype "bidirectional"))
    )
    (net (code "83") (name "unconnected-(U2-PTA16{slash}SPI0_SOUT{slash}UART0_CTS-Pad36)") (class "Default")
      (node (ref "U2") (pin "36") (pinfunction "PTA16/SPI0_SOUT/UART0_CTS_36") (pintype "bidirectional"))
    )
    (net (code "84") (name "unconnected-(U2-PTA17{slash}ADC1_17{slash}SPI0_SIN{slash}UART0_RTS-Pad37)") (class "Default")
      (node (ref "U2") (pin "37") (pinfunction "PTA17/ADC1_17/SPI0_SIN/UART0_RTS_37") (pintype "bidirectional"))
    )
    (net (code "85") (name "unconnected-(U2-PTA18{slash}EXTAL{slash}FTM0_FLT2{slash}FTM_CLKIN0-Pad40)") (class "Default")
      (node (ref "U2") (pin "40") (pinfunction "PTA18/EXTAL/FTM0_FLT2/FTM_CLKIN0_40") (pintype "bidirectional"))
    )
    (net (code "86") (name "unconnected-(U2-PTA19{slash}XTAL{slash}FTM1_FLT0{slash}FTM_CLKIN1-Pad41)") (class "Default")
      (node (ref "U2") (pin "41") (pinfunction "PTA19/XTAL/FTM1_FLT0/FTM_CLKIN1_41") (pintype "bidirectional"))
    )
    (net (code "87") (name "unconnected-(U2-PTC6{slash}SPI0_SOUT-Pad63)") (class "Default")
      (node (ref "U2") (pin "63") (pinfunction "PTC6/SPI0_SOUT_63") (pintype "bidirectional"))
    )
    (net (code "88") (name "unconnected-(U2-PTC7{slash}SPI0_SIN-Pad64)") (class "Default")
      (node (ref "U2") (pin "64") (pinfunction "PTC7/SPI0_SIN_64") (pintype "bidirectional"))
    )
    (net (code "89") (name "unconnected-(U2-PTC8{slash}ADC1_4B-Pad65)") (class "Default")
      (node (ref "U2") (pin "65") (pinfunction "PTC8/ADC1_4B_65") (pintype "bidirectional"))
    )
    (net (code "90") (name "unconnected-(U2-PTC9{slash}ADC1_5B-Pad66)") (class "Default")
      (node (ref "U2") (pin "66") (pinfunction "PTC9/ADC1_5B_66") (pintype "bidirectional"))
    )
    (net (code "91") (name "unconnected-(U2-PTC10{slash}ADC1_6B{slash}I2C1_SCL-Pad67)") (class "Default")
      (node (ref "U2") (pin "67") (pinfunction "PTC10/ADC1_6B/I2C1_SCL_67") (pintype "bidirectional"))
    )
    (net (code "92") (name "unconnected-(U2-PTD7{slash}UART0_TX{slash}FTM0_7-Pad80)") (class "Default")
      (node (ref "U2") (pin "80") (pinfunction "PTD7/UART0_TX/FTM0_7_80") (pintype "bidirectional"))
    )
    (net (code "93") (name "unconnected-(U2-PTE4{slash}SPI1_PCS0{slash}UART3_TX-Pad5)") (class "Default")
      (node (ref "U2") (pin "5") (pinfunction "PTE4/SPI1_PCS0/UART3_TX_5") (pintype "bidirectional"))
    )
    (net (code "94") (name "unconnected-(U2-PTE5{slash}SPI1_PCS2{slash}UART3_RX-Pad6)") (class "Default")
      (node (ref "U2") (pin "6") (pinfunction "PTE5/SPI1_PCS2/UART3_RX_6") (pintype "bidirectional"))
    )
    (net (code "95") (name "unconnected-(U2-VREF_OUT{slash}CMP1_IN5{slash}CMP0_IN5{slash}ADC1_18-Pad21)") (class "Default")
      (node (ref "U2") (pin "21") (pinfunction "VREF_OUT/CMP1_IN5/CMP0_IN5/ADC1_18_21") (pintype "bidirectional"))
    )
  )
)
